# SubHarmonics_Main_Board_v3.net
KiCad netlist of a schematic drawn in EAGLE
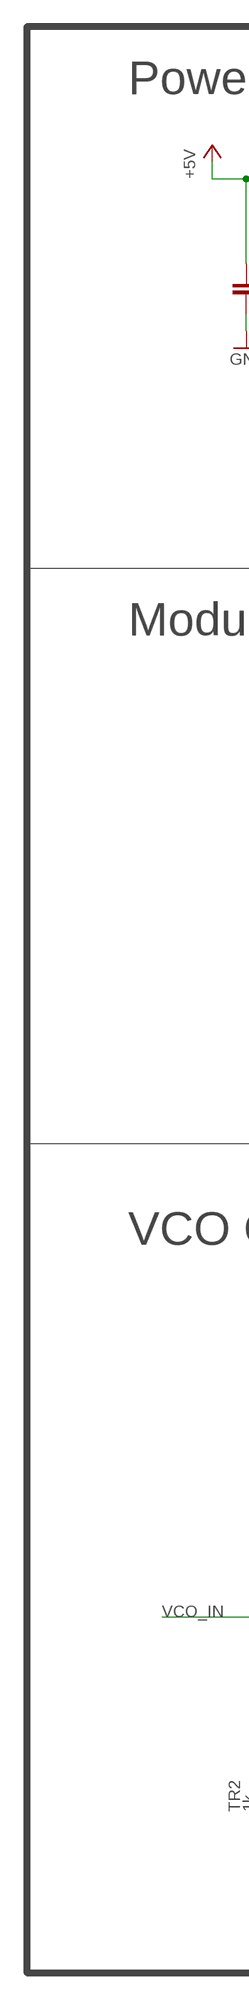
[diagram p0: schematic, sheet 1, part 1 of 2]
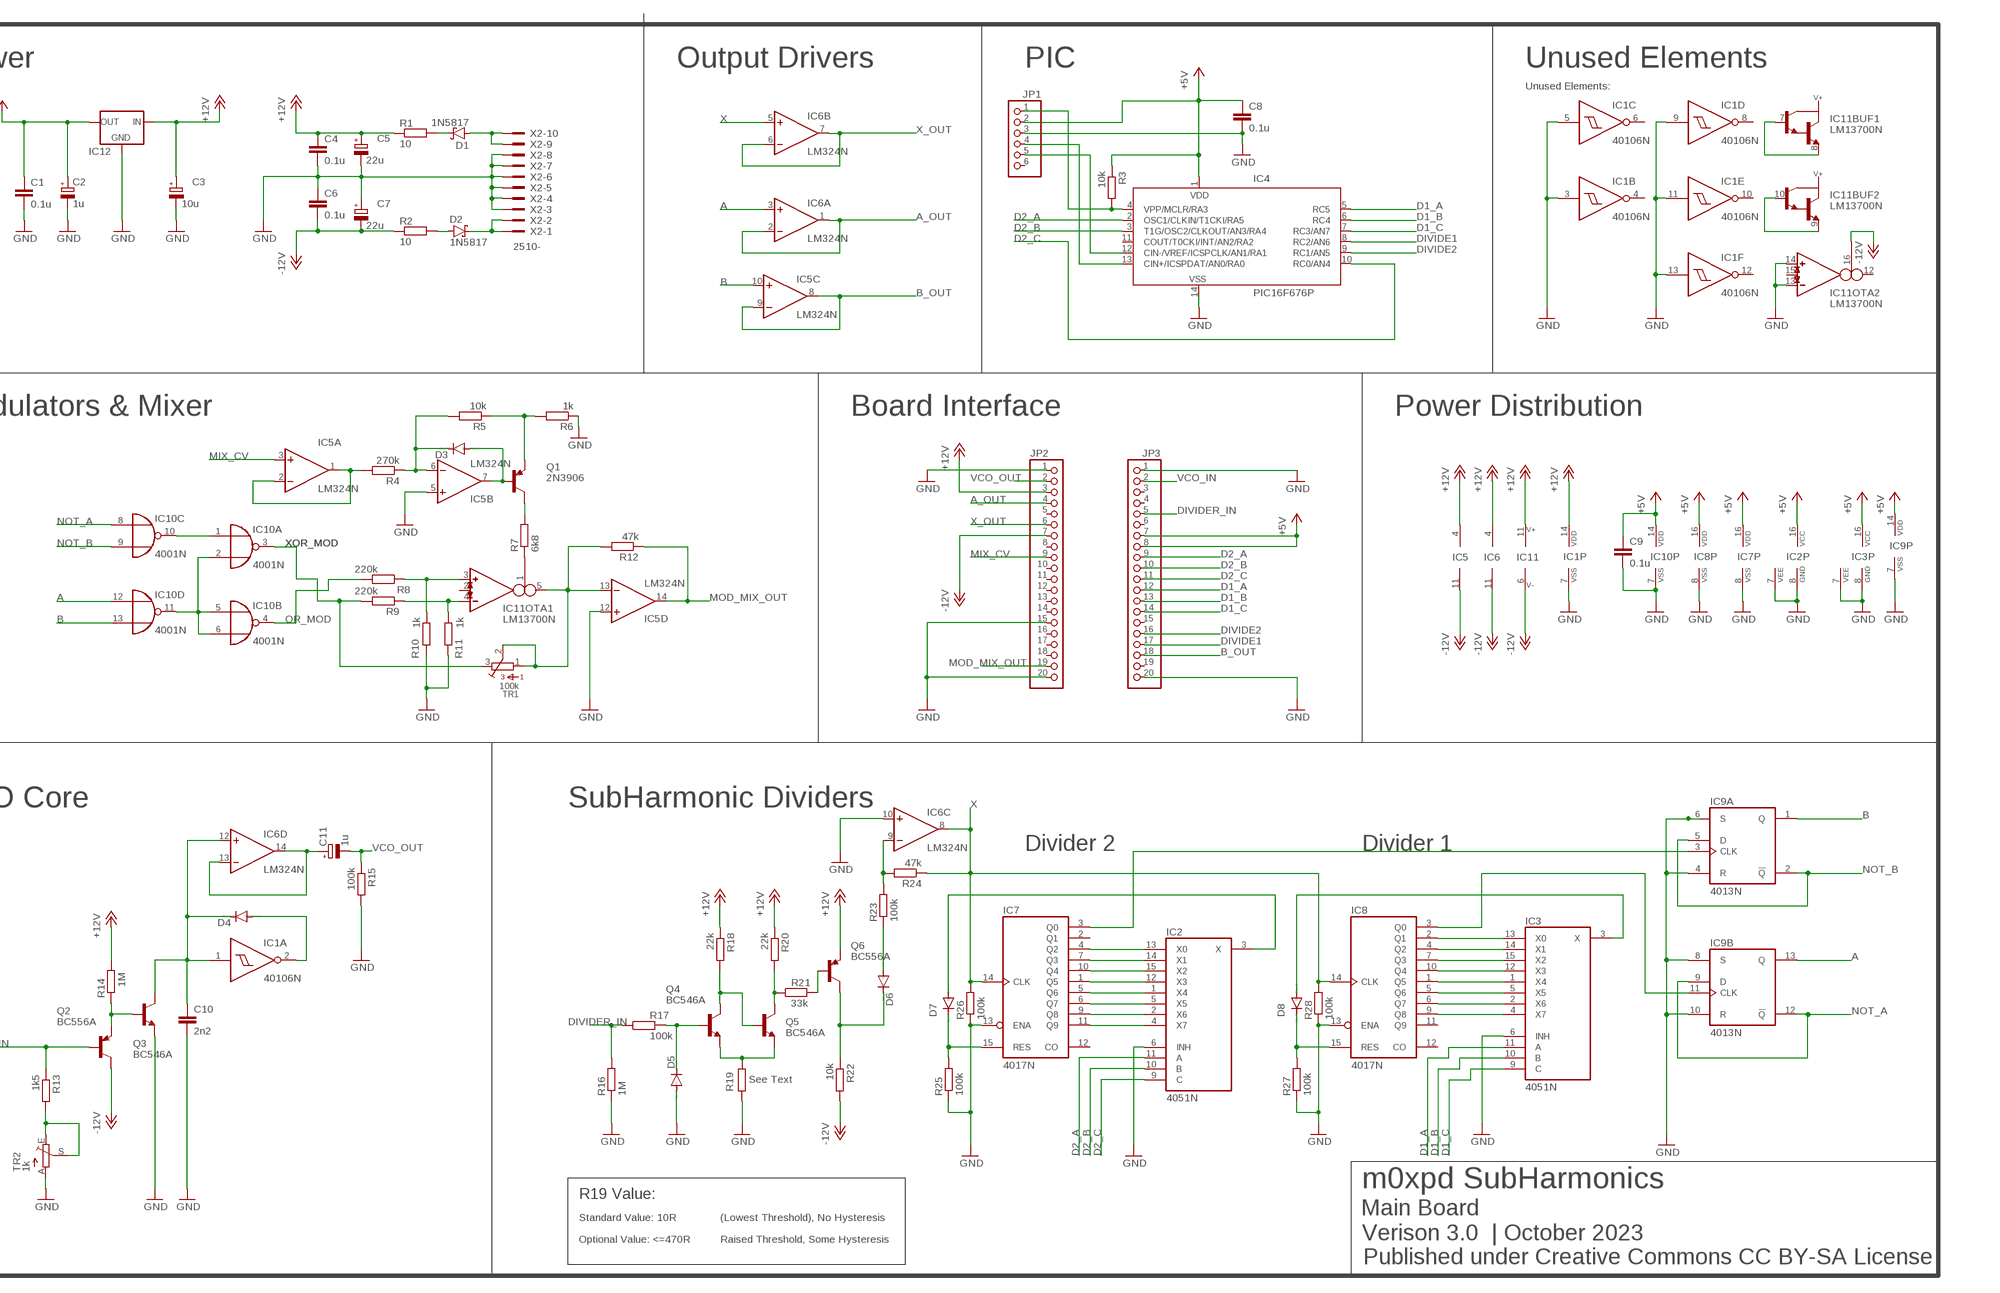
[diagram p1: schematic, sheet 1, part 2 of 2]

(export (version "E")
  (design (tool "Eeschema 10.0.6"))
  (components
    (comp (ref "C1")
      (value "0.1u")
      (footprint "eagle-import:C050-025X075")
      (libsource (lib "eagle-import") (part "C-EU050-025X075"))
    )
    (comp (ref "C2")
      (value "1u")
      (footprint "eagle-import:E2,5-5")
      (libsource (lib "eagle-import") (part "CPOL-EUE2.5-5"))
    )
    (comp (ref "C3")
      (value "10u")
      (footprint "eagle-import:E2,5-5")
      (libsource (lib "eagle-import") (part "CPOL-EUE2.5-5"))
    )
    (comp (ref "C4")
      (value "0.1u")
      (footprint "eagle-import:C050-025X075")
      (libsource (lib "eagle-import") (part "C-EU050-025X075"))
    )
    (comp (ref "C5")
      (value "22u")
      (footprint "eagle-import:E2,5-5")
      (libsource (lib "eagle-import") (part "CPOL-EUE2.5-5"))
    )
    (comp (ref "C6")
      (value "0.1u")
      (footprint "eagle-import:C050-025X075")
      (libsource (lib "eagle-import") (part "C-EU050-025X075"))
    )
    (comp (ref "C7")
      (value "22u")
      (footprint "eagle-import:E2,5-5")
      (libsource (lib "eagle-import") (part "CPOL-EUE2.5-5"))
    )
    (comp (ref "C8")
      (value "0.1u")
      (footprint "eagle-import:C050-025X075")
      (libsource (lib "eagle-import") (part "C-EU050-025X075"))
    )
    (comp (ref "C9")
      (value "0.1u")
      (footprint "eagle-import:C050-025X075")
      (libsource (lib "eagle-import") (part "C-EU050-025X075"))
    )
    (comp (ref "C10")
      (value "2n2")
      (footprint "eagle-import:C050-030X075")
      (libsource (lib "eagle-import") (part "C-EU050-030X075"))
    )
    (comp (ref "C11")
      (value "1u")
      (footprint "eagle-import:E2,5-5")
      (libsource (lib "eagle-import") (part "CPOL-EUE2.5-5"))
    )
    (comp (ref "D1")
      (value "1N5817")
      (footprint "eagle-import:DO35-7")
      (libsource (lib "eagle-import") (part "SCHOTTKY-DIODEDO35-7"))
    )
    (comp (ref "D2")
      (value "1N5817")
      (footprint "eagle-import:DO35-7")
      (libsource (lib "eagle-import") (part "SCHOTTKY-DIODEDO35-7"))
    )
    (comp (ref "D3")
      (value "1N4148DO35-7")
      (footprint "eagle-import:DO35-7")
      (libsource (lib "eagle-import") (part "1N4148DO35-7"))
    )
    (comp (ref "D4")
      (value "1N4148DO35-7")
      (footprint "eagle-import:DO35-7")
      (libsource (lib "eagle-import") (part "1N4148DO35-7"))
    )
    (comp (ref "D5")
      (value "1N4148DO35-7")
      (footprint "eagle-import:DO35-7")
      (libsource (lib "eagle-import") (part "1N4148DO35-7"))
    )
    (comp (ref "D6")
      (value "1N4148DO35-7")
      (footprint "eagle-import:DO35-7")
      (libsource (lib "eagle-import") (part "1N4148DO35-7"))
    )
    (comp (ref "D7")
      (value "1N4148DO35-7")
      (footprint "eagle-import:DO35-7")
      (libsource (lib "eagle-import") (part "1N4148DO35-7"))
    )
    (comp (ref "D8")
      (value "1N4148DO35-7")
      (footprint "eagle-import:DO35-7")
      (libsource (lib "eagle-import") (part "1N4148DO35-7"))
    )
    (comp (ref "IC1")
      (value "40106N")
      (footprint "eagle-import:DIL14")
      (libsource (lib "eagle-import") (part "40106N"))
    )
    (comp (ref "IC2")
      (value "4051N")
      (footprint "eagle-import:DIL16")
      (libsource (lib "eagle-import") (part "4051N"))
    )
    (comp (ref "IC3")
      (value "4051N")
      (footprint "eagle-import:DIL16")
      (libsource (lib "eagle-import") (part "4051N"))
    )
    (comp (ref "IC4")
      (value "PIC16F676P")
      (footprint "eagle-import:DIL14")
      (fields (field (name "MF") "MICROCHIP") (field (name "MPN") "PIC16F676-I/P"))
      (libsource (lib "eagle-import") (part "PIC16F676P"))
    )
    (comp (ref "IC5")
      (value "LM324N")
      (footprint "eagle-import:DIL14")
      (libsource (lib "eagle-import") (part "LM324N"))
    )
    (comp (ref "IC6")
      (value "LM324N")
      (footprint "eagle-import:DIL14")
      (libsource (lib "eagle-import") (part "LM324N"))
    )
    (comp (ref "IC7")
      (value "4017N")
      (footprint "eagle-import:DIL16")
      (libsource (lib "eagle-import") (part "4017N"))
    )
    (comp (ref "IC8")
      (value "4017N")
      (footprint "eagle-import:DIL16")
      (libsource (lib "eagle-import") (part "4017N"))
    )
    (comp (ref "IC9")
      (value "4013N")
      (footprint "eagle-import:DIL14")
      (libsource (lib "eagle-import") (part "4013N"))
    )
    (comp (ref "IC10")
      (value "4001N")
      (footprint "eagle-import:DIL14")
      (libsource (lib "eagle-import") (part "4001N"))
    )
    (comp (ref "IC11")
      (value "LM13700N")
      (footprint "eagle-import:DIL16")
      (libsource (lib "eagle-import") (part "LM13700N"))
    )
    (comp (ref "IC12")
      (value "78LXX")
      (footprint "eagle-import:78LXX")
      (libsource (lib "eagle-import") (part "78LXX"))
    )
    (comp (ref "JP1")
      (value "PINHD-1X6")
      (footprint "eagle-import:1X06")
      (libsource (lib "eagle-import") (part "PINHD-1X6"))
    )
    (comp (ref "JP2")
      (value "PINHD-1X20")
      (footprint "eagle-import:1X20")
      (libsource (lib "eagle-import") (part "PINHD-1X20"))
    )
    (comp (ref "JP3")
      (value "PINHD-1X20")
      (footprint "eagle-import:1X20")
      (libsource (lib "eagle-import") (part "PINHD-1X20"))
    )
    (comp (ref "Q1")
      (value "2N3906")
      (footprint "eagle-import:TO92")
      (libsource (lib "eagle-import") (part "2N3906"))
    )
    (comp (ref "Q2")
      (value "BC556A")
      (footprint "eagle-import:TO92-EBC")
      (libsource (lib "eagle-import") (part "BC556A"))
    )
    (comp (ref "Q3")
      (value "BC546A")
      (footprint "eagle-import:TO92-EBC")
      (libsource (lib "eagle-import") (part "BC546A"))
    )
    (comp (ref "Q4")
      (value "BC546A")
      (footprint "eagle-import:TO92-EBC")
      (libsource (lib "eagle-import") (part "BC546A"))
    )
    (comp (ref "Q5")
      (value "BC546A")
      (footprint "eagle-import:TO92-EBC")
      (libsource (lib "eagle-import") (part "BC546A"))
    )
    (comp (ref "Q6")
      (value "BC556A")
      (footprint "eagle-import:TO92-EBC")
      (libsource (lib "eagle-import") (part "BC556"))
    )
    (comp (ref "R1")
      (value "10")
      (footprint "eagle-import:0204_7")
      (libsource (lib "eagle-import") (part "R-EU_0204/7"))
    )
    (comp (ref "R2")
      (value "10")
      (footprint "eagle-import:0204_7")
      (libsource (lib "eagle-import") (part "R-EU_0204/7"))
    )
    (comp (ref "R3")
      (value "10k")
      (footprint "eagle-import:0204_7")
      (libsource (lib "eagle-import") (part "R-EU_0204/7"))
    )
    (comp (ref "R4")
      (value "270k")
      (footprint "eagle-import:0204_7")
      (libsource (lib "eagle-import") (part "R-EU_0204/7"))
    )
    (comp (ref "R5")
      (value "10k")
      (footprint "eagle-import:0204_7")
      (libsource (lib "eagle-import") (part "R-EU_0204/7"))
    )
    (comp (ref "R6")
      (value "1k")
      (footprint "eagle-import:0204_7")
      (libsource (lib "eagle-import") (part "R-EU_0204/7"))
    )
    (comp (ref "R7")
      (value "6k8")
      (footprint "eagle-import:0204_7")
      (libsource (lib "eagle-import") (part "R-EU_0204/7"))
    )
    (comp (ref "R8")
      (value "220k")
      (footprint "eagle-import:0204_7")
      (libsource (lib "eagle-import") (part "R-EU_0204/7"))
    )
    (comp (ref "R9")
      (value "220k")
      (footprint "eagle-import:0204_7")
      (libsource (lib "eagle-import") (part "R-EU_0204/7"))
    )
    (comp (ref "R10")
      (value "1k")
      (footprint "eagle-import:0204_7")
      (libsource (lib "eagle-import") (part "R-EU_0204/7"))
    )
    (comp (ref "R11")
      (value "1k")
      (footprint "eagle-import:0204_7")
      (libsource (lib "eagle-import") (part "R-EU_0204/7"))
    )
    (comp (ref "R12")
      (value "47k")
      (footprint "eagle-import:0204_7")
      (libsource (lib "eagle-import") (part "R-EU_0204/7"))
    )
    (comp (ref "R13")
      (value "1k5")
      (footprint "eagle-import:0204_7")
      (libsource (lib "eagle-import") (part "R-EU_0204/7"))
    )
    (comp (ref "R14")
      (value "1M")
      (footprint "eagle-import:0204_7")
      (libsource (lib "eagle-import") (part "R-EU_0204/7"))
    )
    (comp (ref "R15")
      (value "100k")
      (footprint "eagle-import:0204_7")
      (libsource (lib "eagle-import") (part "R-EU_0204/7"))
    )
    (comp (ref "R16")
      (value "1M")
      (footprint "eagle-import:0204_7")
      (libsource (lib "eagle-import") (part "R-EU_0204/7"))
    )
    (comp (ref "R17")
      (value "100k")
      (footprint "eagle-import:0204_7")
      (libsource (lib "eagle-import") (part "R-EU_0204/7"))
    )
    (comp (ref "R18")
      (value "22k")
      (footprint "eagle-import:0204_7")
      (libsource (lib "eagle-import") (part "R-EU_0204/7"))
    )
    (comp (ref "R19")
      (value "See Text")
      (footprint "eagle-import:0204_7")
      (libsource (lib "eagle-import") (part "R-EU_0204/7"))
    )
    (comp (ref "R20")
      (value "22k")
      (footprint "eagle-import:0204_7")
      (libsource (lib "eagle-import") (part "R-EU_0204/7"))
    )
    (comp (ref "R21")
      (value "33k")
      (footprint "eagle-import:0204_7")
      (libsource (lib "eagle-import") (part "R-EU_0204/7"))
    )
    (comp (ref "R22")
      (value "10k")
      (footprint "eagle-import:0204_7")
      (libsource (lib "eagle-import") (part "R-EU_0204/7"))
    )
    (comp (ref "R23")
      (value "100k")
      (footprint "eagle-import:0204_7")
      (libsource (lib "eagle-import") (part "R-EU_0204/7"))
    )
    (comp (ref "R24")
      (value "47k")
      (footprint "eagle-import:0204_7")
      (libsource (lib "eagle-import") (part "R-EU_0204/7"))
    )
    (comp (ref "R25")
      (value "100k")
      (footprint "eagle-import:0204_7")
      (libsource (lib "eagle-import") (part "R-EU_0204/7"))
    )
    (comp (ref "R26")
      (value "100k")
      (footprint "eagle-import:0204_7")
      (libsource (lib "eagle-import") (part "R-EU_0204/7"))
    )
    (comp (ref "R27")
      (value "100k")
      (footprint "eagle-import:0204_7")
      (libsource (lib "eagle-import") (part "R-EU_0204/7"))
    )
    (comp (ref "R28")
      (value "100k")
      (footprint "eagle-import:0204_7")
      (libsource (lib "eagle-import") (part "R-EU_0204/7"))
    )
    (comp (ref "TR1")
      (value "100k")
      (footprint "eagle-import:BOURNS_3362P_TRIMMER")
      (libsource (lib "eagle-import") (part "BOURNS_3362P_TRIMMERP"))
    )
    (comp (ref "TR2")
      (value "1k")
      (footprint "eagle-import:B64Y")
      (libsource (lib "eagle-import") (part "TRIM_EU-B64Y"))
    )
    (comp (ref "X2")
      (value "2510-")
      (footprint "eagle-import:PAK100_2500-10")
      (fields (field (name "MF") "3M") (field (name "MPN") "2510-6002UB"))
      (libsource (lib "eagle-import") (part "2510-"))
    )
  )
  (nets
    (net (code "1") (name "+5V") (class "Default")
      (node (ref "C1") (pin "1") (pinfunction "1_1") (pintype "passive"))
      (node (ref "C2") (pin "+") (pinfunction "+_+") (pintype "passive"))
      (node (ref "C8") (pin "1") (pinfunction "1_1") (pintype "passive"))
      (node (ref "C9") (pin "1") (pinfunction "1_1") (pintype "passive"))
      (node (ref "IC10") (pin "14") (pinfunction "VDD_14") (pintype "power_in"))
      (node (ref "IC12") (pin "OUT") (pinfunction "OUT_OUT") (pintype "passive"))
      (node (ref "IC2") (pin "16") (pinfunction "VCC_16") (pintype "power_in"))
      (node (ref "IC3") (pin "16") (pinfunction "VCC_16") (pintype "power_in"))
      (node (ref "IC4") (pin "1") (pinfunction "VDD_1") (pintype "power_in"))
      (node (ref "IC7") (pin "16") (pinfunction "VDD_16") (pintype "power_in"))
      (node (ref "IC8") (pin "16") (pinfunction "VDD_16") (pintype "power_in"))
      (node (ref "IC9") (pin "14") (pinfunction "VDD_14") (pintype "power_in"))
      (node (ref "JP1") (pin "2") (pinfunction "2_2") (pintype "passive"))
      (node (ref "JP3") (pin "7") (pinfunction "7_7") (pintype "passive"))
      (node (ref "JP3") (pin "8") (pinfunction "8_8") (pintype "passive"))
      (node (ref "R3") (pin "1") (pinfunction "1_1") (pintype "passive"))
    )
    (net (code "2") (name "+12V") (class "Default")
      (node (ref "C3") (pin "+") (pinfunction "+_+") (pintype "passive"))
      (node (ref "C4") (pin "1") (pinfunction "1_1") (pintype "passive"))
      (node (ref "C5") (pin "+") (pinfunction "+_+") (pintype "passive"))
      (node (ref "IC1") (pin "14") (pinfunction "VDD_14") (pintype "power_in"))
      (node (ref "IC11") (pin "11") (pinfunction "V+_11") (pintype "power_in"))
      (node (ref "IC12") (pin "IN") (pinfunction "IN_IN") (pintype "input"))
      (node (ref "IC5") (pin "4") (pinfunction "V+_4") (pintype "power_in"))
      (node (ref "IC6") (pin "4") (pinfunction "V+_4") (pintype "power_in"))
      (node (ref "JP2") (pin "3") (pinfunction "3_3") (pintype "passive"))
      (node (ref "Q6") (pin "E") (pinfunction "E_E") (pintype "passive"))
      (node (ref "R1") (pin "1") (pinfunction "1_1") (pintype "passive"))
      (node (ref "R14") (pin "2") (pinfunction "2_2") (pintype "passive"))
      (node (ref "R18") (pin "1") (pinfunction "1_1") (pintype "passive"))
      (node (ref "R20") (pin "1") (pinfunction "1_1") (pintype "passive"))
    )
    (net (code "3") (name "-12V") (class "Default")
      (node (ref "C6") (pin "2") (pinfunction "2_2") (pintype "passive"))
      (node (ref "C7") (pin "-") (pinfunction "-_-") (pintype "passive"))
      (node (ref "IC11") (pin "16") (pinfunction "I_BIAS_16") (pintype "input"))
      (node (ref "IC11") (pin "6") (pinfunction "V-_6") (pintype "power_in"))
      (node (ref "IC5") (pin "11") (pinfunction "V-_11") (pintype "power_in"))
      (node (ref "IC6") (pin "11") (pinfunction "V-_11") (pintype "power_in"))
      (node (ref "JP2") (pin "7") (pinfunction "7_7") (pintype "passive"))
      (node (ref "Q2") (pin "C") (pinfunction "C_C") (pintype "passive"))
      (node (ref "R2") (pin "1") (pinfunction "1_1") (pintype "passive"))
      (node (ref "R22") (pin "2") (pinfunction "2_2") (pintype "passive"))
    )
    (net (code "4") (name "/A") (class "Default")
      (node (ref "IC10") (pin "12") (pinfunction "I0_12") (pintype "input"))
      (node (ref "IC6") (pin "3") (pinfunction "+IN_3") (pintype "input"))
      (node (ref "IC9") (pin "13") (pinfunction "Q_13") (pintype "output"))
    )
    (net (code "5") (name "/A_OUT") (class "Default")
      (node (ref "IC6") (pin "1") (pinfunction "OUT_1") (pintype "output"))
      (node (ref "IC6") (pin "2") (pinfunction "-IN_2") (pintype "input"))
      (node (ref "JP2") (pin "4") (pinfunction "4_4") (pintype "passive"))
    )
    (net (code "6") (name "/B") (class "Default")
      (node (ref "IC10") (pin "13") (pinfunction "I1_13") (pintype "input"))
      (node (ref "IC5") (pin "10") (pinfunction "+IN_10") (pintype "input"))
      (node (ref "IC9") (pin "1") (pinfunction "Q_1") (pintype "output"))
    )
    (net (code "7") (name "/B_OUT") (class "Default")
      (node (ref "IC5") (pin "8") (pinfunction "OUT_8") (pintype "output"))
      (node (ref "IC5") (pin "9") (pinfunction "-IN_9") (pintype "input"))
      (node (ref "JP3") (pin "18") (pinfunction "18_18") (pintype "passive"))
    )
    (net (code "8") (name "/D1_A") (class "Default")
      (node (ref "IC3") (pin "11") (pinfunction "A_11") (pintype "input"))
      (node (ref "IC4") (pin "5") (pinfunction "RC5_5") (pintype "bidirectional"))
      (node (ref "JP3") (pin "12") (pinfunction "12_12") (pintype "passive"))
    )
    (net (code "9") (name "/D1_B") (class "Default")
      (node (ref "IC3") (pin "10") (pinfunction "B_10") (pintype "input"))
      (node (ref "IC4") (pin "6") (pinfunction "RC4_6") (pintype "bidirectional"))
      (node (ref "JP3") (pin "13") (pinfunction "13_13") (pintype "passive"))
    )
    (net (code "10") (name "/D1_C") (class "Default")
      (node (ref "IC3") (pin "9") (pinfunction "C_9") (pintype "input"))
      (node (ref "IC4") (pin "7") (pinfunction "RC3/AN7_7") (pintype "bidirectional"))
      (node (ref "JP3") (pin "14") (pinfunction "14_14") (pintype "passive"))
    )
    (net (code "11") (name "/D2_A") (class "Default")
      (node (ref "IC2") (pin "11") (pinfunction "A_11") (pintype "input"))
      (node (ref "IC4") (pin "2") (pinfunction "OSC1/CLKIN/T1CKI/RA5_2") (pintype "bidirectional"))
      (node (ref "JP3") (pin "9") (pinfunction "9_9") (pintype "passive"))
    )
    (net (code "12") (name "/D2_B") (class "Default")
      (node (ref "IC2") (pin "10") (pinfunction "B_10") (pintype "input"))
      (node (ref "IC4") (pin "3") (pinfunction "T1G/OSC2/CLKOUT/AN3/RA4_3") (pintype "bidirectional"))
      (node (ref "JP3") (pin "10") (pinfunction "10_10") (pintype "passive"))
    )
    (net (code "13") (name "/D2_C") (class "Default")
      (node (ref "IC2") (pin "9") (pinfunction "C_9") (pintype "input"))
      (node (ref "IC4") (pin "10") (pinfunction "RC0/AN4_10") (pintype "bidirectional"))
      (node (ref "JP3") (pin "11") (pinfunction "11_11") (pintype "passive"))
    )
    (net (code "14") (name "/DIVIDE1") (class "Default")
      (node (ref "IC4") (pin "8") (pinfunction "RC2/AN6_8") (pintype "bidirectional"))
      (node (ref "JP3") (pin "17") (pinfunction "17_17") (pintype "passive"))
    )
    (net (code "15") (name "/DIVIDE2") (class "Default")
      (node (ref "IC4") (pin "9") (pinfunction "RC1/AN5_9") (pintype "bidirectional"))
      (node (ref "JP3") (pin "16") (pinfunction "16_16") (pintype "passive"))
    )
    (net (code "16") (name "/DIVIDER_IN") (class "Default")
      (node (ref "JP3") (pin "5") (pinfunction "5_5") (pintype "passive"))
      (node (ref "R16") (pin "2") (pinfunction "2_2") (pintype "passive"))
      (node (ref "R17") (pin "1") (pinfunction "1_1") (pintype "passive"))
    )
    (net (code "17") (name "/MIX_CV") (class "Default")
      (node (ref "IC5") (pin "3") (pinfunction "+IN_3") (pintype "input"))
      (node (ref "JP2") (pin "9") (pinfunction "9_9") (pintype "passive"))
    )
    (net (code "18") (name "/MOD_MIX_OUT") (class "Default")
      (node (ref "IC5") (pin "14") (pinfunction "OUT_14") (pintype "output"))
      (node (ref "JP2") (pin "19") (pinfunction "19_19") (pintype "passive"))
      (node (ref "R12") (pin "1") (pinfunction "1_1") (pintype "passive"))
    )
    (net (code "19") (name "/NOT_A") (class "Default")
      (node (ref "IC10") (pin "8") (pinfunction "I0_8") (pintype "input"))
      (node (ref "IC9") (pin "12") (pinfunction "~{Q}_12") (pintype "output"))
      (node (ref "IC9") (pin "9") (pinfunction "D_9") (pintype "input"))
    )
    (net (code "20") (name "/NOT_B") (class "Default")
      (node (ref "IC10") (pin "9") (pinfunction "I1_9") (pintype "input"))
      (node (ref "IC9") (pin "2") (pinfunction "~{Q}_2") (pintype "output"))
      (node (ref "IC9") (pin "5") (pinfunction "D_5") (pintype "input"))
    )
    (net (code "21") (name "/OR_MOD") (class "Default")
      (node (ref "IC10") (pin "4") (pinfunction "O_4") (pintype "output"))
      (node (ref "R8") (pin "2") (pinfunction "2_2") (pintype "passive"))
    )
    (net (code "22") (name "/VCO_IN") (class "Default")
      (node (ref "JP3") (pin "2") (pinfunction "2_2") (pintype "passive"))
      (node (ref "Q2") (pin "B") (pinfunction "B_B") (pintype "passive"))
      (node (ref "R13") (pin "1") (pinfunction "1_1") (pintype "passive"))
    )
    (net (code "23") (name "/VCO_OUT") (class "Default")
      (node (ref "C11") (pin "-") (pinfunction "-_-") (pintype "passive"))
      (node (ref "JP2") (pin "2") (pinfunction "2_2") (pintype "passive"))
      (node (ref "R15") (pin "1") (pinfunction "1_1") (pintype "passive"))
    )
    (net (code "24") (name "/X") (class "Default")
      (node (ref "IC6") (pin "5") (pinfunction "+IN_5") (pintype "input"))
      (node (ref "IC6") (pin "8") (pinfunction "OUT_8") (pintype "output"))
      (node (ref "IC7") (pin "14") (pinfunction "CLK_14") (pintype "input"))
      (node (ref "IC8") (pin "14") (pinfunction "CLK_14") (pintype "input"))
      (node (ref "R24") (pin "1") (pinfunction "1_1") (pintype "passive"))
      (node (ref "R26") (pin "2") (pinfunction "2_2") (pintype "passive"))
      (node (ref "R28") (pin "2") (pinfunction "2_2") (pintype "passive"))
    )
    (net (code "25") (name "/XOR_MOD") (class "Default")
      (node (ref "IC10") (pin "3") (pinfunction "O_3") (pintype "output"))
      (node (ref "R9") (pin "2") (pinfunction "2_2") (pintype "passive"))
      (node (ref "TR1") (pin "3") (pinfunction "3_3") (pintype "passive"))
    )
    (net (code "26") (name "/X_OUT") (class "Default")
      (node (ref "IC6") (pin "6") (pinfunction "-IN_6") (pintype "input"))
      (node (ref "IC6") (pin "7") (pinfunction "OUT_7") (pintype "output"))
      (node (ref "JP2") (pin "6") (pinfunction "6_6") (pintype "passive"))
    )
    (net (code "27") (name "GND") (class "Default")
      (node (ref "C1") (pin "2") (pinfunction "2_2") (pintype "passive"))
      (node (ref "C10") (pin "2") (pinfunction "2_2") (pintype "passive"))
      (node (ref "C2") (pin "-") (pinfunction "-_-") (pintype "passive"))
      (node (ref "C3") (pin "-") (pinfunction "-_-") (pintype "passive"))
      (node (ref "C4") (pin "2") (pinfunction "2_2") (pintype "passive"))
      (node (ref "C5") (pin "-") (pinfunction "-_-") (pintype "passive"))
      (node (ref "C6") (pin "1") (pinfunction "1_1") (pintype "passive"))
      (node (ref "C7") (pin "+") (pinfunction "+_+") (pintype "passive"))
      (node (ref "C8") (pin "2") (pinfunction "2_2") (pintype "passive"))
      (node (ref "C9") (pin "2") (pinfunction "2_2") (pintype "passive"))
      (node (ref "D5") (pin "A") (pinfunction "A_A") (pintype "passive"))
      (node (ref "IC1") (pin "11") (pinfunction "I_11") (pintype "input"))
      (node (ref "IC1") (pin "13") (pinfunction "I_13") (pintype "input"))
      (node (ref "IC1") (pin "3") (pinfunction "I_3") (pintype "input"))
      (node (ref "IC1") (pin "5") (pinfunction "I_5") (pintype "input"))
      (node (ref "IC1") (pin "7") (pinfunction "VSS_7") (pintype "power_in"))
      (node (ref "IC1") (pin "9") (pinfunction "I_9") (pintype "input"))
      (node (ref "IC10") (pin "7") (pinfunction "VSS_7") (pintype "power_in"))
      (node (ref "IC11") (pin "13") (pinfunction "IN_N_13") (pintype "input"))
      (node (ref "IC11") (pin "14") (pinfunction "IN_P_14") (pintype "input"))
      (node (ref "IC12") (pin "GND") (pinfunction "GND_GND") (pintype "input"))
      (node (ref "IC2") (pin "6") (pinfunction "INH_6") (pintype "input"))
      (node (ref "IC2") (pin "7") (pinfunction "VEE_7") (pintype "power_in"))
      (node (ref "IC2") (pin "8") (pinfunction "GND_8") (pintype "power_in"))
      (node (ref "IC3") (pin "6") (pinfunction "INH_6") (pintype "input"))
      (node (ref "IC3") (pin "7") (pinfunction "VEE_7") (pintype "power_in"))
      (node (ref "IC3") (pin "8") (pinfunction "GND_8") (pintype "power_in"))
      (node (ref "IC4") (pin "14") (pinfunction "VSS_14") (pintype "power_in"))
      (node (ref "IC5") (pin "12") (pinfunction "+IN_12") (pintype "input"))
      (node (ref "IC5") (pin "5") (pinfunction "+IN_5") (pintype "input"))
      (node (ref "IC6") (pin "10") (pinfunction "+IN_10") (pintype "input"))
      (node (ref "IC7") (pin "13") (pinfunction "ENA_13") (pintype "input"))
      (node (ref "IC7") (pin "8") (pinfunction "VSS_8") (pintype "power_in"))
      (node (ref "IC8") (pin "13") (pinfunction "ENA_13") (pintype "input"))
      (node (ref "IC8") (pin "8") (pinfunction "VSS_8") (pintype "power_in"))
      (node (ref "IC9") (pin "10") (pinfunction "R_10") (pintype "input"))
      (node (ref "IC9") (pin "4") (pinfunction "R_4") (pintype "input"))
      (node (ref "IC9") (pin "6") (pinfunction "S_6") (pintype "input"))
      (node (ref "IC9") (pin "7") (pinfunction "VSS_7") (pintype "power_in"))
      (node (ref "IC9") (pin "8") (pinfunction "S_8") (pintype "input"))
      (node (ref "JP1") (pin "3") (pinfunction "3_3") (pintype "passive"))
      (node (ref "JP2") (pin "1") (pinfunction "1_1") (pintype "passive"))
      (node (ref "JP2") (pin "15") (pinfunction "15_15") (pintype "passive"))
      (node (ref "JP2") (pin "20") (pinfunction "20_20") (pintype "passive"))
      (node (ref "JP3") (pin "1") (pinfunction "1_1") (pintype "passive"))
      (node (ref "JP3") (pin "20") (pinfunction "20_20") (pintype "passive"))
      (node (ref "Q3") (pin "E") (pinfunction "E_E") (pintype "passive"))
      (node (ref "R10") (pin "2") (pinfunction "2_2") (pintype "passive"))
      (node (ref "R11") (pin "2") (pinfunction "2_2") (pintype "passive"))
      (node (ref "R15") (pin "2") (pinfunction "2_2") (pintype "passive"))
      (node (ref "R16") (pin "1") (pinfunction "1_1") (pintype "passive"))
      (node (ref "R19") (pin "2") (pinfunction "2_2") (pintype "passive"))
      (node (ref "R25") (pin "1") (pinfunction "1_1") (pintype "passive"))
      (node (ref "R26") (pin "1") (pinfunction "1_1") (pintype "passive"))
      (node (ref "R27") (pin "1") (pinfunction "1_1") (pintype "passive"))
      (node (ref "R28") (pin "1") (pinfunction "1_1") (pintype "passive"))
      (node (ref "R6") (pin "1") (pinfunction "1_1") (pintype "passive"))
      (node (ref "TR2") (pin "A") (pinfunction "A_A") (pintype "passive"))
      (node (ref "X2") (pin "3") (pinfunction "KL_3") (pintype "passive"))
      (node (ref "X2") (pin "4") (pinfunction "KL_4") (pintype "passive"))
      (node (ref "X2") (pin "5") (pinfunction "KL_5") (pintype "passive"))
      (node (ref "X2") (pin "6") (pinfunction "KL_6") (pintype "passive"))
      (node (ref "X2") (pin "7") (pinfunction "KL_7") (pintype "passive"))
      (node (ref "X2") (pin "8") (pinfunction "KL_8") (pintype "passive"))
    )
    (net (code "28") (name "Net-(D1-PadC)") (class "Default")
      (node (ref "D1") (pin "C") (pinfunction "C_C") (pintype "passive"))
      (node (ref "R1") (pin "2") (pinfunction "2_2") (pintype "passive"))
    )
    (net (code "29") (name "Net-(D2-PadA)") (class "Default")
      (node (ref "D2") (pin "A") (pinfunction "A_A") (pintype "passive"))
      (node (ref "R2") (pin "2") (pinfunction "2_2") (pintype "passive"))
    )
    (net (code "30") (name "Net-(D5-PadC)") (class "Default")
      (node (ref "D5") (pin "C") (pinfunction "C_C") (pintype "passive"))
      (node (ref "Q4") (pin "B") (pinfunction "B_B") (pintype "passive"))
      (node (ref "R17") (pin "2") (pinfunction "2_2") (pintype "passive"))
    )
    (net (code "31") (name "Net-(D6-PadA)") (class "Default")
      (node (ref "D6") (pin "A") (pinfunction "A_A") (pintype "passive"))
      (node (ref "R23") (pin "1") (pinfunction "1_1") (pintype "passive"))
    )
    (net (code "32") (name "Net-(D6-PadC)") (class "Default")
      (node (ref "D6") (pin "C") (pinfunction "C_C") (pintype "passive"))
      (node (ref "Q6") (pin "C") (pinfunction "C_C") (pintype "passive"))
      (node (ref "R22") (pin "1") (pinfunction "1_1") (pintype "passive"))
    )
    (net (code "33") (name "Net-(IC1A-I)") (class "Default")
      (node (ref "C10") (pin "1") (pinfunction "1_1") (pintype "passive"))
      (node (ref "D4") (pin "C") (pinfunction "C_C") (pintype "passive"))
      (node (ref "IC1") (pin "1") (pinfunction "I_1") (pintype "input"))
      (node (ref "IC6") (pin "12") (pinfunction "+IN_12") (pintype "input"))
      (node (ref "Q3") (pin "C") (pinfunction "C_C") (pintype "passive"))
    )
    (net (code "34") (name "Net-(IC1A-O)") (class "Default")
      (node (ref "D4") (pin "A") (pinfunction "A_A") (pintype "passive"))
      (node (ref "IC1") (pin "2") (pinfunction "O_2") (pintype "output"))
    )
    (net (code "35") (name "Net-(IC2A-X)") (class "Default")
      (node (ref "D7") (pin "A") (pinfunction "A_A") (pintype "passive"))
      (node (ref "IC2") (pin "3") (pinfunction "X_3") (pintype "bidirectional"))
    )
    (net (code "36") (name "Net-(IC2A-X0)") (class "Default")
      (node (ref "IC2") (pin "13") (pinfunction "X0_13") (pintype "bidirectional"))
      (node (ref "IC7") (pin "4") (pinfunction "Q2_4") (pintype "output"))
    )
    (net (code "37") (name "Net-(IC2A-X1)") (class "Default")
      (node (ref "IC2") (pin "14") (pinfunction "X1_14") (pintype "bidirectional"))
      (node (ref "IC7") (pin "7") (pinfunction "Q3_7") (pintype "output"))
    )
    (net (code "38") (name "Net-(IC2A-X2)") (class "Default")
      (node (ref "IC2") (pin "15") (pinfunction "X2_15") (pintype "bidirectional"))
      (node (ref "IC7") (pin "10") (pinfunction "Q4_10") (pintype "output"))
    )
    (net (code "39") (name "Net-(IC2A-X3)") (class "Default")
      (node (ref "IC2") (pin "12") (pinfunction "X3_12") (pintype "bidirectional"))
      (node (ref "IC7") (pin "1") (pinfunction "Q5_1") (pintype "output"))
    )
    (net (code "40") (name "Net-(IC2A-X4)") (class "Default")
      (node (ref "IC2") (pin "1") (pinfunction "X4_1") (pintype "bidirectional"))
      (node (ref "IC7") (pin "5") (pinfunction "Q6_5") (pintype "output"))
    )
    (net (code "41") (name "Net-(IC2A-X5)") (class "Default")
      (node (ref "IC2") (pin "5") (pinfunction "X5_5") (pintype "bidirectional"))
      (node (ref "IC7") (pin "6") (pinfunction "Q7_6") (pintype "output"))
    )
    (net (code "42") (name "Net-(IC2A-X6)") (class "Default")
      (node (ref "IC2") (pin "2") (pinfunction "X6_2") (pintype "bidirectional"))
      (node (ref "IC7") (pin "9") (pinfunction "Q8_9") (pintype "output"))
    )
    (net (code "43") (name "Net-(IC2A-X7)") (class "Default")
      (node (ref "IC2") (pin "4") (pinfunction "X7_4") (pintype "bidirectional"))
      (node (ref "IC7") (pin "11") (pinfunction "Q9_11") (pintype "output"))
    )
    (net (code "44") (name "Net-(IC3A-X)") (class "Default")
      (node (ref "D8") (pin "A") (pinfunction "A_A") (pintype "passive"))
      (node (ref "IC3") (pin "3") (pinfunction "X_3") (pintype "bidirectional"))
    )
    (net (code "45") (name "Net-(IC3A-X0)") (class "Default")
      (node (ref "IC3") (pin "13") (pinfunction "X0_13") (pintype "bidirectional"))
      (node (ref "IC8") (pin "2") (pinfunction "Q1_2") (pintype "output"))
    )
    (net (code "46") (name "Net-(IC3A-X1)") (class "Default")
      (node (ref "IC3") (pin "14") (pinfunction "X1_14") (pintype "bidirectional"))
      (node (ref "IC8") (pin "4") (pinfunction "Q2_4") (pintype "output"))
    )
    (net (code "47") (name "Net-(IC3A-X2)") (class "Default")
      (node (ref "IC3") (pin "15") (pinfunction "X2_15") (pintype "bidirectional"))
      (node (ref "IC8") (pin "7") (pinfunction "Q3_7") (pintype "output"))
    )
    (net (code "48") (name "Net-(IC3A-X3)") (class "Default")
      (node (ref "IC3") (pin "12") (pinfunction "X3_12") (pintype "bidirectional"))
      (node (ref "IC8") (pin "10") (pinfunction "Q4_10") (pintype "output"))
    )
    (net (code "49") (name "Net-(IC3A-X4)") (class "Default")
      (node (ref "IC3") (pin "1") (pinfunction "X4_1") (pintype "bidirectional"))
      (node (ref "IC8") (pin "1") (pinfunction "Q5_1") (pintype "output"))
    )
    (net (code "50") (name "Net-(IC3A-X5)") (class "Default")
      (node (ref "IC3") (pin "5") (pinfunction "X5_5") (pintype "bidirectional"))
      (node (ref "IC8") (pin "5") (pinfunction "Q6_5") (pintype "output"))
    )
    (net (code "51") (name "Net-(IC3A-X6)") (class "Default")
      (node (ref "IC3") (pin "2") (pinfunction "X6_2") (pintype "bidirectional"))
      (node (ref "IC8") (pin "6") (pinfunction "Q7_6") (pintype "output"))
    )
    (net (code "52") (name "Net-(IC3A-X7)") (class "Default")
      (node (ref "IC3") (pin "4") (pinfunction "X7_4") (pintype "bidirectional"))
      (node (ref "IC8") (pin "9") (pinfunction "Q8_9") (pintype "output"))
    )
    (net (code "53") (name "Net-(IC4-CIN+{slash}ICSPDAT{slash}AN0{slash}RA0)") (class "Default")
      (node (ref "IC4") (pin "13") (pinfunction "CIN+/ICSPDAT/AN0/RA0_13") (pintype "bidirectional"))
      (node (ref "JP1") (pin "4") (pinfunction "4_4") (pintype "passive"))
    )
    (net (code "54") (name "Net-(IC4-CIN-{slash}VREF{slash}ICSPCLK{slash}AN1{slash}RA1)") (class "Default")
      (node (ref "IC4") (pin "12") (pinfunction "CIN-/VREF/ICSPCLK/AN1/RA1_12") (pintype "bidirectional"))
      (node (ref "JP1") (pin "5") (pinfunction "5_5") (pintype "passive"))
    )
    (net (code "55") (name "Net-(IC4-VPP{slash}MCLR{slash}RA3)") (class "Default")
      (node (ref "IC4") (pin "4") (pinfunction "VPP/MCLR/RA3_4") (pintype "input"))
      (node (ref "JP1") (pin "1") (pinfunction "1_1") (pintype "passive"))
      (node (ref "R3") (pin "2") (pinfunction "2_2") (pintype "passive"))
    )
    (net (code "56") (name "Net-(IC5A--IN)") (class "Default")
      (node (ref "IC5") (pin "1") (pinfunction "OUT_1") (pintype "output"))
      (node (ref "IC5") (pin "2") (pinfunction "-IN_2") (pintype "input"))
      (node (ref "R4") (pin "2") (pinfunction "2_2") (pintype "passive"))
    )
    (net (code "57") (name "Net-(IC5B--IN)") (class "Default")
      (node (ref "D3") (pin "C") (pinfunction "C_C") (pintype "passive"))
      (node (ref "IC5") (pin "6") (pinfunction "-IN_6") (pintype "input"))
      (node (ref "R4") (pin "1") (pinfunction "1_1") (pintype "passive"))
      (node (ref "R5") (pin "2") (pinfunction "2_2") (pintype "passive"))
    )
    (net (code "58") (name "Net-(IC5B-OUT)") (class "Default")
      (node (ref "D3") (pin "A") (pinfunction "A_A") (pintype "passive"))
      (node (ref "IC5") (pin "7") (pinfunction "OUT_7") (pintype "output"))
      (node (ref "Q1") (pin "2") (pinfunction "B_2") (pintype "passive"))
    )
    (net (code "59") (name "Net-(IC6C--IN)") (class "Default")
      (node (ref "IC6") (pin "9") (pinfunction "-IN_9") (pintype "input"))
      (node (ref "R23") (pin "2") (pinfunction "2_2") (pintype "passive"))
      (node (ref "R24") (pin "2") (pinfunction "2_2") (pintype "passive"))
    )
    (net (code "60") (name "Net-(IC6D--IN)") (class "Default")
      (node (ref "C11") (pin "+") (pinfunction "+_+") (pintype "passive"))
      (node (ref "IC6") (pin "13") (pinfunction "-IN_13") (pintype "input"))
      (node (ref "IC6") (pin "14") (pinfunction "OUT_14") (pintype "output"))
    )
    (net (code "61") (name "Net-(IC7A-Q0)") (class "Default")
      (node (ref "IC7") (pin "3") (pinfunction "Q0_3") (pintype "output"))
      (node (ref "IC9") (pin "3") (pinfunction "CLK_3") (pintype "input"))
    )
    (net (code "62") (name "Net-(IC7A-RES)") (class "Default")
      (node (ref "D7") (pin "C") (pinfunction "C_C") (pintype "passive"))
      (node (ref "IC7") (pin "15") (pinfunction "RES_15") (pintype "input"))
      (node (ref "R25") (pin "2") (pinfunction "2_2") (pintype "passive"))
    )
    (net (code "63") (name "Net-(IC8A-Q0)") (class "Default")
      (node (ref "IC8") (pin "3") (pinfunction "Q0_3") (pintype "output"))
      (node (ref "IC9") (pin "11") (pinfunction "CLK_11") (pintype "input"))
    )
    (net (code "64") (name "Net-(IC8A-RES)") (class "Default")
      (node (ref "D8") (pin "C") (pinfunction "C_C") (pintype "passive"))
      (node (ref "IC8") (pin "15") (pinfunction "RES_15") (pintype "input"))
      (node (ref "R27") (pin "2") (pinfunction "2_2") (pintype "passive"))
    )
    (net (code "65") (name "Net-(IC10A-I0)") (class "Default")
      (node (ref "IC10") (pin "1") (pinfunction "I0_1") (pintype "input"))
      (node (ref "IC10") (pin "10") (pinfunction "O_10") (pintype "output"))
    )
    (net (code "66") (name "Net-(IC10A-I1)") (class "Default")
      (node (ref "IC10") (pin "11") (pinfunction "O_11") (pintype "output"))
      (node (ref "IC10") (pin "2") (pinfunction "I1_2") (pintype "input"))
      (node (ref "IC10") (pin "5") (pinfunction "I0_5") (pintype "input"))
      (node (ref "IC10") (pin "6") (pinfunction "I1_6") (pintype "input"))
    )
    (net (code "67") (name "Net-(IC11A-B)") (class "Default")
      (node (ref "IC11") (pin "7") (pinfunction "B_7") (pintype "passive"))
      (node (ref "IC11") (pin "8") (pinfunction "E_8") (pintype "passive"))
    )
    (net (code "68") (name "Net-(IC11B-B)") (class "Default")
      (node (ref "IC11") (pin "10") (pinfunction "B_10") (pintype "passive"))
      (node (ref "IC11") (pin "9") (pinfunction "E_9") (pintype "passive"))
    )
    (net (code "69") (name "Net-(IC11C-IN_N)") (class "Default")
      (node (ref "IC11") (pin "4") (pinfunction "IN_N_4") (pintype "input"))
      (node (ref "R11") (pin "1") (pinfunction "1_1") (pintype "passive"))
      (node (ref "R9") (pin "1") (pinfunction "1_1") (pintype "passive"))
    )
    (net (code "70") (name "Net-(IC11C-IN_P)") (class "Default")
      (node (ref "IC11") (pin "3") (pinfunction "IN_P_3") (pintype "input"))
      (node (ref "R10") (pin "1") (pinfunction "1_1") (pintype "passive"))
      (node (ref "R8") (pin "1") (pinfunction "1_1") (pintype "passive"))
    )
    (net (code "71") (name "Net-(IC11C-I_BIAS)") (class "Default")
      (node (ref "IC11") (pin "1") (pinfunction "I_BIAS_1") (pintype "input"))
      (node (ref "R7") (pin "1") (pinfunction "1_1") (pintype "passive"))
    )
    (net (code "72") (name "Net-(IC11C-OUT)") (class "Default")
      (node (ref "IC11") (pin "5") (pinfunction "OUT_5") (pintype "output"))
      (node (ref "IC5") (pin "13") (pinfunction "-IN_13") (pintype "input"))
      (node (ref "R12") (pin "2") (pinfunction "2_2") (pintype "passive"))
      (node (ref "TR1") (pin "1") (pinfunction "1_1") (pintype "passive"))
      (node (ref "TR1") (pin "2") (pinfunction "2_2") (pintype "passive"))
    )
    (net (code "73") (name "Net-(Q1-C)") (class "Default")
      (node (ref "Q1") (pin "1") (pinfunction "C_1") (pintype "passive"))
      (node (ref "R7") (pin "2") (pinfunction "2_2") (pintype "passive"))
    )
    (net (code "74") (name "Net-(Q1-E)") (class "Default")
      (node (ref "Q1") (pin "3") (pinfunction "E_3") (pintype "passive"))
      (node (ref "R5") (pin "1") (pinfunction "1_1") (pintype "passive"))
      (node (ref "R6") (pin "2") (pinfunction "2_2") (pintype "passive"))
    )
    (net (code "75") (name "Net-(Q2-PadE)") (class "Default")
      (node (ref "Q2") (pin "E") (pinfunction "E_E") (pintype "passive"))
      (node (ref "Q3") (pin "B") (pinfunction "B_B") (pintype "passive"))
      (node (ref "R14") (pin "1") (pinfunction "1_1") (pintype "passive"))
    )
    (net (code "76") (name "Net-(Q4-PadC)") (class "Default")
      (node (ref "Q4") (pin "C") (pinfunction "C_C") (pintype "passive"))
      (node (ref "Q5") (pin "B") (pinfunction "B_B") (pintype "passive"))
      (node (ref "R18") (pin "2") (pinfunction "2_2") (pintype "passive"))
    )
    (net (code "77") (name "Net-(Q4-PadE)") (class "Default")
      (node (ref "Q4") (pin "E") (pinfunction "E_E") (pintype "passive"))
      (node (ref "Q5") (pin "E") (pinfunction "E_E") (pintype "passive"))
      (node (ref "R19") (pin "1") (pinfunction "1_1") (pintype "passive"))
    )
    (net (code "78") (name "Net-(Q5-PadC)") (class "Default")
      (node (ref "Q5") (pin "C") (pinfunction "C_C") (pintype "passive"))
      (node (ref "R20") (pin "2") (pinfunction "2_2") (pintype "passive"))
      (node (ref "R21") (pin "1") (pinfunction "1_1") (pintype "passive"))
    )
    (net (code "79") (name "Net-(Q6-PadB)") (class "Default")
      (node (ref "Q6") (pin "B") (pinfunction "B_B") (pintype "passive"))
      (node (ref "R21") (pin "2") (pinfunction "2_2") (pintype "passive"))
    )
    (net (code "80") (name "Net-(R13-Pad2)") (class "Default")
      (node (ref "R13") (pin "2") (pinfunction "2_2") (pintype "passive"))
      (node (ref "TR2") (pin "E") (pinfunction "E_E") (pintype "passive"))
      (node (ref "TR2") (pin "S") (pinfunction "S_S") (pintype "passive"))
    )
    (net (code "81") (name "Net-(X2A-KL)") (class "Default")
      (node (ref "D2") (pin "C") (pinfunction "C_C") (pintype "passive"))
      (node (ref "X2") (pin "1") (pinfunction "KL_1") (pintype "passive"))
      (node (ref "X2") (pin "2") (pinfunction "KL_2") (pintype "passive"))
    )
    (net (code "82") (name "Net-(X2B-KL)") (class "Default")
      (node (ref "D1") (pin "A") (pinfunction "A_A") (pintype "passive"))
      (node (ref "X2") (pin "10") (pinfunction "KL_10") (pintype "passive"))
      (node (ref "X2") (pin "9") (pinfunction "KL_9") (pintype "passive"))
    )
    (net (code "83") (name "unconnected-(IC1B-O-Pad4)") (class "Default")
      (node (ref "IC1") (pin "4") (pinfunction "O_4") (pintype "output"))
    )
    (net (code "84") (name "unconnected-(IC1C-O-Pad6)") (class "Default")
      (node (ref "IC1") (pin "6") (pinfunction "O_6") (pintype "output"))
    )
    (net (code "85") (name "unconnected-(IC1D-O-Pad8)") (class "Default")
      (node (ref "IC1") (pin "8") (pinfunction "O_8") (pintype "output"))
    )
    (net (code "86") (name "unconnected-(IC1E-O-Pad10)") (class "Default")
      (node (ref "IC1") (pin "10") (pinfunction "O_10") (pintype "output"))
    )
    (net (code "87") (name "unconnected-(IC1F-O-Pad12)") (class "Default")
      (node (ref "IC1") (pin "12") (pinfunction "O_12") (pintype "output"))
    )
    (net (code "88") (name "unconnected-(IC4-COUT{slash}T0CKI{slash}INT{slash}AN2{slash}RA2-Pad11)") (class "Default")
      (node (ref "IC4") (pin "11") (pinfunction "COUT/T0CKI/INT/AN2/RA2_11") (pintype "bidirectional"))
    )
    (net (code "89") (name "unconnected-(IC7A-CO-Pad12)") (class "Default")
      (node (ref "IC7") (pin "12") (pinfunction "CO_12") (pintype "output"))
    )
    (net (code "90") (name "unconnected-(IC7A-Q1-Pad2)") (class "Default")
      (node (ref "IC7") (pin "2") (pinfunction "Q1_2") (pintype "output"))
    )
    (net (code "91") (name "unconnected-(IC8A-CO-Pad12)") (class "Default")
      (node (ref "IC8") (pin "12") (pinfunction "CO_12") (pintype "output"))
    )
    (net (code "92") (name "unconnected-(IC8A-Q9-Pad11)") (class "Default")
      (node (ref "IC8") (pin "11") (pinfunction "Q9_11") (pintype "output"))
    )
    (net (code "93") (name "unconnected-(IC11C-I_DIODE-Pad2)") (class "Default")
      (node (ref "IC11") (pin "2") (pinfunction "I_DIODE_2") (pintype "input"))
    )
    (net (code "94") (name "unconnected-(IC11D-I_DIODE-Pad15)") (class "Default")
      (node (ref "IC11") (pin "15") (pinfunction "I_DIODE_15") (pintype "input"))
    )
    (net (code "95") (name "unconnected-(IC11D-OUT-Pad12)") (class "Default")
      (node (ref "IC11") (pin "12") (pinfunction "OUT_12") (pintype "output"))
    )
    (net (code "96") (name "unconnected-(JP1-Pad6)") (class "Default")
      (node (ref "JP1") (pin "6") (pinfunction "6_6") (pintype "passive"))
    )
    (net (code "97") (name "unconnected-(JP2-Pad5)") (class "Default")
      (node (ref "JP2") (pin "5") (pinfunction "5_5") (pintype "passive"))
    )
    (net (code "98") (name "unconnected-(JP2-Pad8)") (class "Default")
      (node (ref "JP2") (pin "8") (pinfunction "8_8") (pintype "passive"))
    )
    (net (code "99") (name "unconnected-(JP2-Pad10)") (class "Default")
      (node (ref "JP2") (pin "10") (pinfunction "10_10") (pintype "passive"))
    )
    (net (code "100") (name "unconnected-(JP2-Pad11)") (class "Default")
      (node (ref "JP2") (pin "11") (pinfunction "11_11") (pintype "passive"))
    )
    (net (code "101") (name "unconnected-(JP2-Pad12)") (class "Default")
      (node (ref "JP2") (pin "12") (pinfunction "12_12") (pintype "passive"))
    )
    (net (code "102") (name "unconnected-(JP2-Pad13)") (class "Default")
      (node (ref "JP2") (pin "13") (pinfunction "13_13") (pintype "passive"))
    )
    (net (code "103") (name "unconnected-(JP2-Pad14)") (class "Default")
      (node (ref "JP2") (pin "14") (pinfunction "14_14") (pintype "passive"))
    )
    (net (code "104") (name "unconnected-(JP2-Pad16)") (class "Default")
      (node (ref "JP2") (pin "16") (pinfunction "16_16") (pintype "passive"))
    )
    (net (code "105") (name "unconnected-(JP2-Pad17)") (class "Default")
      (node (ref "JP2") (pin "17") (pinfunction "17_17") (pintype "passive"))
    )
    (net (code "106") (name "unconnected-(JP2-Pad18)") (class "Default")
      (node (ref "JP2") (pin "18") (pinfunction "18_18") (pintype "passive"))
    )
    (net (code "107") (name "unconnected-(JP3-Pad3)") (class "Default")
      (node (ref "JP3") (pin "3") (pinfunction "3_3") (pintype "passive"))
    )
    (net (code "108") (name "unconnected-(JP3-Pad4)") (class "Default")
      (node (ref "JP3") (pin "4") (pinfunction "4_4") (pintype "passive"))
    )
    (net (code "109") (name "unconnected-(JP3-Pad6)") (class "Default")
      (node (ref "JP3") (pin "6") (pinfunction "6_6") (pintype "passive"))
    )
    (net (code "110") (name "unconnected-(JP3-Pad15)") (class "Default")
      (node (ref "JP3") (pin "15") (pinfunction "15_15") (pintype "passive"))
    )
    (net (code "111") (name "unconnected-(JP3-Pad19)") (class "Default")
      (node (ref "JP3") (pin "19") (pinfunction "19_19") (pintype "passive"))
    )
  )
)
